# frontpanel-new.net
KiCad netlist of a schematic drawn in EAGLE
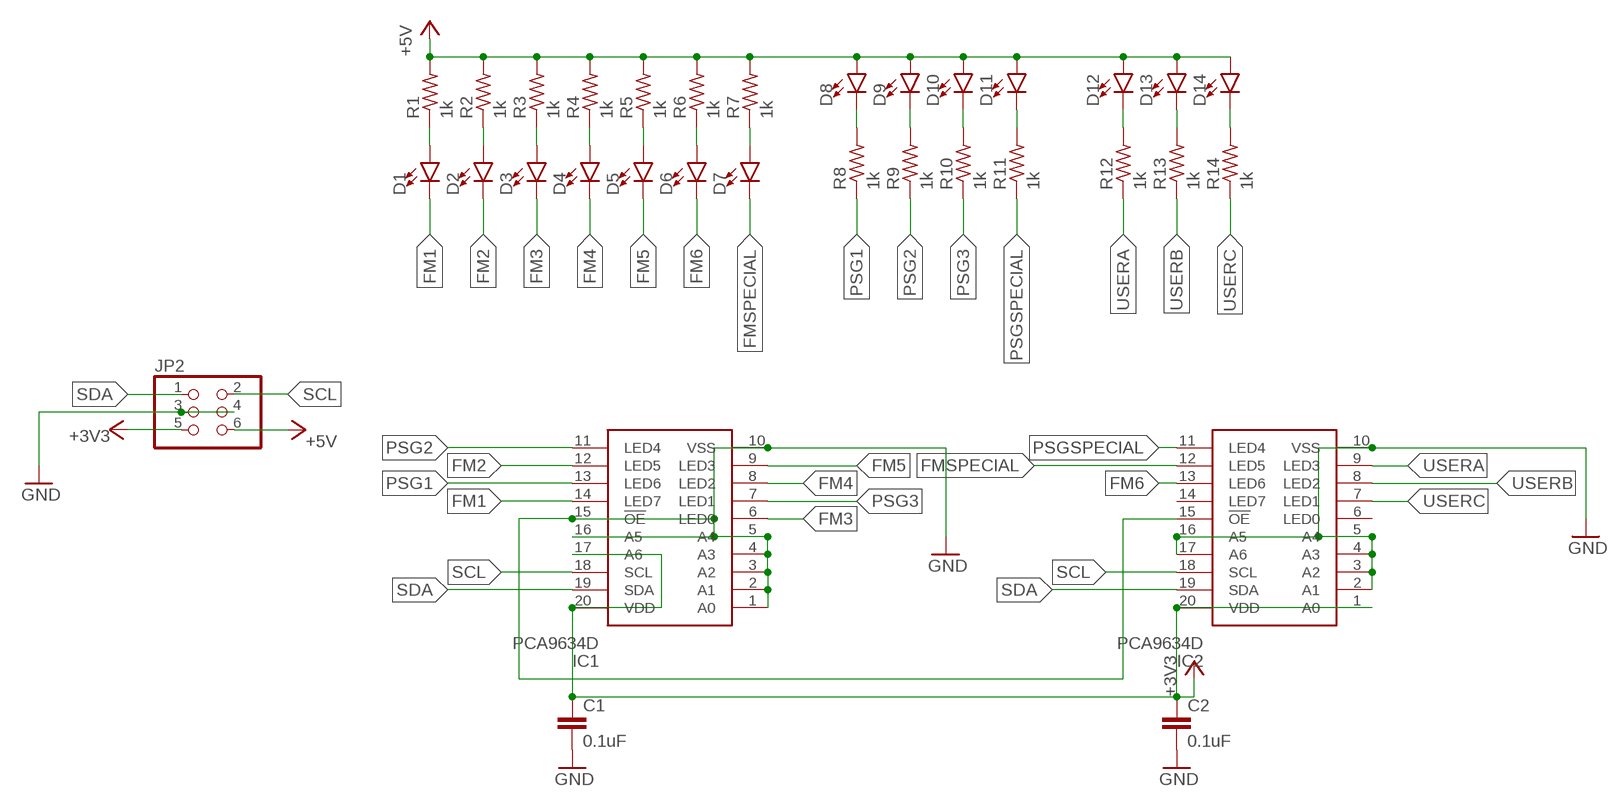
[diagram p0: schematic, sheet 1]

(export (version "E")
  (design (tool "Eeschema 10.0.6"))
  (components
    (comp (ref "C1")
      (value "0.1uF")
      (footprint "eagle-import:C0805")
      (libsource (lib "eagle-import") (part "C-EUC0805"))
    )
    (comp (ref "C2")
      (value "0.1uF")
      (footprint "eagle-import:C0805")
      (libsource (lib "eagle-import") (part "C-EUC0805"))
    )
    (comp (ref "D1")
      (value "AM2520")
      (footprint "eagle-import:AM2520HOLE")
      (libsource (lib "eagle-import") (part "AM2520"))
    )
    (comp (ref "D2")
      (value "AM2520")
      (footprint "eagle-import:AM2520HOLE")
      (libsource (lib "eagle-import") (part "AM2520"))
    )
    (comp (ref "D3")
      (value "AM2520")
      (footprint "eagle-import:AM2520HOLE")
      (libsource (lib "eagle-import") (part "AM2520"))
    )
    (comp (ref "D4")
      (value "AM2520")
      (footprint "eagle-import:AM2520HOLE")
      (libsource (lib "eagle-import") (part "AM2520"))
    )
    (comp (ref "D5")
      (value "AM2520")
      (footprint "eagle-import:AM2520HOLE")
      (libsource (lib "eagle-import") (part "AM2520"))
    )
    (comp (ref "D6")
      (value "AM2520")
      (footprint "eagle-import:AM2520HOLE")
      (libsource (lib "eagle-import") (part "AM2520"))
    )
    (comp (ref "D7")
      (value "AM2520")
      (footprint "eagle-import:AM2520HOLE")
      (libsource (lib "eagle-import") (part "AM2520"))
    )
    (comp (ref "D8")
      (value "AM2520")
      (footprint "eagle-import:AM2520HOLE")
      (libsource (lib "eagle-import") (part "AM2520"))
    )
    (comp (ref "D9")
      (value "AM2520")
      (footprint "eagle-import:AM2520HOLE")
      (libsource (lib "eagle-import") (part "AM2520"))
    )
    (comp (ref "D10")
      (value "AM2520")
      (footprint "eagle-import:AM2520HOLE")
      (libsource (lib "eagle-import") (part "AM2520"))
    )
    (comp (ref "D11")
      (value "AM2520")
      (footprint "eagle-import:AM2520HOLE")
      (libsource (lib "eagle-import") (part "AM2520"))
    )
    (comp (ref "D12")
      (value "AM2520")
      (footprint "eagle-import:AM2520HOLE")
      (libsource (lib "eagle-import") (part "AM2520"))
    )
    (comp (ref "D13")
      (value "AM2520")
      (footprint "eagle-import:AM2520HOLE")
      (libsource (lib "eagle-import") (part "AM2520"))
    )
    (comp (ref "D14")
      (value "AM2520")
      (footprint "eagle-import:AM2520HOLE")
      (libsource (lib "eagle-import") (part "AM2520"))
    )
    (comp (ref "IC1")
      (value "PCA9634D")
      (footprint "eagle-import:SOIC127P1032X265-20N")
      (libsource (lib "eagle-import") (part "PCA9634D"))
    )
    (comp (ref "IC2")
      (value "PCA9634D")
      (footprint "eagle-import:SOIC127P1032X265-20N")
      (libsource (lib "eagle-import") (part "PCA9634D"))
    )
    (comp (ref "JP2")
      (value "PINHD-2X3SMT")
      (footprint "eagle-import:2X03_SMT")
      (libsource (lib "eagle-import") (part "PINHD-2X3SMT"))
    )
    (comp (ref "R1")
      (value "1k")
      (footprint "eagle-import:R0805")
      (libsource (lib "eagle-import") (part "R-US_R0805"))
    )
    (comp (ref "R2")
      (value "1k")
      (footprint "eagle-import:R0805")
      (libsource (lib "eagle-import") (part "R-US_R0805"))
    )
    (comp (ref "R3")
      (value "1k")
      (footprint "eagle-import:R0805")
      (libsource (lib "eagle-import") (part "R-US_R0805"))
    )
    (comp (ref "R4")
      (value "1k")
      (footprint "eagle-import:R0805")
      (libsource (lib "eagle-import") (part "R-US_R0805"))
    )
    (comp (ref "R5")
      (value "1k")
      (footprint "eagle-import:R0805")
      (libsource (lib "eagle-import") (part "R-US_R0805"))
    )
    (comp (ref "R6")
      (value "1k")
      (footprint "eagle-import:R0805")
      (libsource (lib "eagle-import") (part "R-US_R0805"))
    )
    (comp (ref "R7")
      (value "1k")
      (footprint "eagle-import:R0805")
      (libsource (lib "eagle-import") (part "R-US_R0805"))
    )
    (comp (ref "R8")
      (value "1k")
      (footprint "eagle-import:R0805")
      (libsource (lib "eagle-import") (part "R-US_R0805"))
    )
    (comp (ref "R9")
      (value "1k")
      (footprint "eagle-import:R0805")
      (libsource (lib "eagle-import") (part "R-US_R0805"))
    )
    (comp (ref "R10")
      (value "1k")
      (footprint "eagle-import:R0805")
      (libsource (lib "eagle-import") (part "R-US_R0805"))
    )
    (comp (ref "R11")
      (value "1k")
      (footprint "eagle-import:R0805")
      (libsource (lib "eagle-import") (part "R-US_R0805"))
    )
    (comp (ref "R12")
      (value "1k")
      (footprint "eagle-import:R0805")
      (libsource (lib "eagle-import") (part "R-US_R0805"))
    )
    (comp (ref "R13")
      (value "1k")
      (footprint "eagle-import:R0805")
      (libsource (lib "eagle-import") (part "R-US_R0805"))
    )
    (comp (ref "R14")
      (value "1k")
      (footprint "eagle-import:R0805")
      (libsource (lib "eagle-import") (part "R-US_R0805"))
    )
  )
  (nets
    (net (code "1") (name "+3V3") (class "Default")
      (node (ref "C1") (pin "1") (pinfunction "1_1") (pintype "passive"))
      (node (ref "C2") (pin "1") (pinfunction "1_1") (pintype "passive"))
      (node (ref "IC1") (pin "17") (pinfunction "A6_17") (pintype "bidirectional"))
      (node (ref "IC1") (pin "20") (pinfunction "VDD_20") (pintype "power_in"))
      (node (ref "IC2") (pin "1") (pinfunction "A0_1") (pintype "bidirectional"))
      (node (ref "IC2") (pin "20") (pinfunction "VDD_20") (pintype "power_in"))
      (node (ref "JP2") (pin "5") (pinfunction "5_5") (pintype "passive"))
    )
    (net (code "2") (name "+5V") (class "Default")
      (node (ref "D10") (pin "A") (pinfunction "A_A") (pintype "passive"))
      (node (ref "D11") (pin "A") (pinfunction "A_A") (pintype "passive"))
      (node (ref "D12") (pin "A") (pinfunction "A_A") (pintype "passive"))
      (node (ref "D13") (pin "A") (pinfunction "A_A") (pintype "passive"))
      (node (ref "D14") (pin "A") (pinfunction "A_A") (pintype "passive"))
      (node (ref "D8") (pin "A") (pinfunction "A_A") (pintype "passive"))
      (node (ref "D9") (pin "A") (pinfunction "A_A") (pintype "passive"))
      (node (ref "JP2") (pin "6") (pinfunction "6_6") (pintype "passive"))
      (node (ref "R1") (pin "2") (pinfunction "2_2") (pintype "passive"))
      (node (ref "R2") (pin "2") (pinfunction "2_2") (pintype "passive"))
      (node (ref "R3") (pin "2") (pinfunction "2_2") (pintype "passive"))
      (node (ref "R4") (pin "2") (pinfunction "2_2") (pintype "passive"))
      (node (ref "R5") (pin "2") (pinfunction "2_2") (pintype "passive"))
      (node (ref "R6") (pin "2") (pinfunction "2_2") (pintype "passive"))
      (node (ref "R7") (pin "2") (pinfunction "2_2") (pintype "passive"))
    )
    (net (code "3") (name "FM1") (class "Default")
      (node (ref "D1") (pin "C") (pinfunction "C_C") (pintype "passive"))
      (node (ref "IC1") (pin "14") (pinfunction "LED7_14") (pintype "bidirectional"))
    )
    (net (code "4") (name "FM2") (class "Default")
      (node (ref "D2") (pin "C") (pinfunction "C_C") (pintype "passive"))
      (node (ref "IC1") (pin "12") (pinfunction "LED5_12") (pintype "bidirectional"))
    )
    (net (code "5") (name "FM3") (class "Default")
      (node (ref "D3") (pin "C") (pinfunction "C_C") (pintype "passive"))
      (node (ref "IC1") (pin "6") (pinfunction "LED0_6") (pintype "bidirectional"))
    )
    (net (code "6") (name "FM4") (class "Default")
      (node (ref "D4") (pin "C") (pinfunction "C_C") (pintype "passive"))
      (node (ref "IC1") (pin "8") (pinfunction "LED2_8") (pintype "bidirectional"))
    )
    (net (code "7") (name "FM5") (class "Default")
      (node (ref "D5") (pin "C") (pinfunction "C_C") (pintype "passive"))
      (node (ref "IC1") (pin "9") (pinfunction "LED3_9") (pintype "bidirectional"))
    )
    (net (code "8") (name "FM6") (class "Default")
      (node (ref "D6") (pin "C") (pinfunction "C_C") (pintype "passive"))
      (node (ref "IC2") (pin "13") (pinfunction "LED6_13") (pintype "bidirectional"))
    )
    (net (code "9") (name "FMSPECIAL") (class "Default")
      (node (ref "D7") (pin "C") (pinfunction "C_C") (pintype "passive"))
      (node (ref "IC2") (pin "12") (pinfunction "LED5_12") (pintype "bidirectional"))
    )
    (net (code "10") (name "GND") (class "Default")
      (node (ref "C1") (pin "2") (pinfunction "2_2") (pintype "passive"))
      (node (ref "C2") (pin "2") (pinfunction "2_2") (pintype "passive"))
      (node (ref "IC1") (pin "1") (pinfunction "A0_1") (pintype "bidirectional"))
      (node (ref "IC1") (pin "10") (pinfunction "VSS_10") (pintype "power_in"))
      (node (ref "IC1") (pin "15") (pinfunction "~{OE}_15") (pintype "bidirectional"))
      (node (ref "IC1") (pin "16") (pinfunction "A5_16") (pintype "bidirectional"))
      (node (ref "IC1") (pin "2") (pinfunction "A1_2") (pintype "bidirectional"))
      (node (ref "IC1") (pin "3") (pinfunction "A2_3") (pintype "bidirectional"))
      (node (ref "IC1") (pin "4") (pinfunction "A3_4") (pintype "bidirectional"))
      (node (ref "IC1") (pin "5") (pinfunction "A4_5") (pintype "bidirectional"))
      (node (ref "IC2") (pin "10") (pinfunction "VSS_10") (pintype "power_in"))
      (node (ref "IC2") (pin "15") (pinfunction "~{OE}_15") (pintype "bidirectional"))
      (node (ref "IC2") (pin "16") (pinfunction "A5_16") (pintype "bidirectional"))
      (node (ref "IC2") (pin "17") (pinfunction "A6_17") (pintype "bidirectional"))
      (node (ref "IC2") (pin "2") (pinfunction "A1_2") (pintype "bidirectional"))
      (node (ref "IC2") (pin "3") (pinfunction "A2_3") (pintype "bidirectional"))
      (node (ref "IC2") (pin "4") (pinfunction "A3_4") (pintype "bidirectional"))
      (node (ref "IC2") (pin "5") (pinfunction "A4_5") (pintype "bidirectional"))
      (node (ref "JP2") (pin "3") (pinfunction "3_3") (pintype "passive"))
      (node (ref "JP2") (pin "4") (pinfunction "4_4") (pintype "passive"))
    )
    (net (code "11") (name "Net-(D1-PadA)") (class "Default")
      (node (ref "D1") (pin "A") (pinfunction "A_A") (pintype "passive"))
      (node (ref "R1") (pin "1") (pinfunction "1_1") (pintype "passive"))
    )
    (net (code "12") (name "Net-(D2-PadA)") (class "Default")
      (node (ref "D2") (pin "A") (pinfunction "A_A") (pintype "passive"))
      (node (ref "R2") (pin "1") (pinfunction "1_1") (pintype "passive"))
    )
    (net (code "13") (name "Net-(D3-PadA)") (class "Default")
      (node (ref "D3") (pin "A") (pinfunction "A_A") (pintype "passive"))
      (node (ref "R3") (pin "1") (pinfunction "1_1") (pintype "passive"))
    )
    (net (code "14") (name "Net-(D4-PadA)") (class "Default")
      (node (ref "D4") (pin "A") (pinfunction "A_A") (pintype "passive"))
      (node (ref "R4") (pin "1") (pinfunction "1_1") (pintype "passive"))
    )
    (net (code "15") (name "Net-(D5-PadA)") (class "Default")
      (node (ref "D5") (pin "A") (pinfunction "A_A") (pintype "passive"))
      (node (ref "R5") (pin "1") (pinfunction "1_1") (pintype "passive"))
    )
    (net (code "16") (name "Net-(D6-PadA)") (class "Default")
      (node (ref "D6") (pin "A") (pinfunction "A_A") (pintype "passive"))
      (node (ref "R6") (pin "1") (pinfunction "1_1") (pintype "passive"))
    )
    (net (code "17") (name "Net-(D7-PadA)") (class "Default")
      (node (ref "D7") (pin "A") (pinfunction "A_A") (pintype "passive"))
      (node (ref "R7") (pin "1") (pinfunction "1_1") (pintype "passive"))
    )
    (net (code "18") (name "Net-(D8-PadC)") (class "Default")
      (node (ref "D8") (pin "C") (pinfunction "C_C") (pintype "passive"))
      (node (ref "R8") (pin "2") (pinfunction "2_2") (pintype "passive"))
    )
    (net (code "19") (name "Net-(D9-PadC)") (class "Default")
      (node (ref "D9") (pin "C") (pinfunction "C_C") (pintype "passive"))
      (node (ref "R9") (pin "2") (pinfunction "2_2") (pintype "passive"))
    )
    (net (code "20") (name "Net-(D10-PadC)") (class "Default")
      (node (ref "D10") (pin "C") (pinfunction "C_C") (pintype "passive"))
      (node (ref "R10") (pin "2") (pinfunction "2_2") (pintype "passive"))
    )
    (net (code "21") (name "Net-(D11-PadC)") (class "Default")
      (node (ref "D11") (pin "C") (pinfunction "C_C") (pintype "passive"))
      (node (ref "R11") (pin "2") (pinfunction "2_2") (pintype "passive"))
    )
    (net (code "22") (name "Net-(D12-PadC)") (class "Default")
      (node (ref "D12") (pin "C") (pinfunction "C_C") (pintype "passive"))
      (node (ref "R12") (pin "2") (pinfunction "2_2") (pintype "passive"))
    )
    (net (code "23") (name "Net-(D13-PadC)") (class "Default")
      (node (ref "D13") (pin "C") (pinfunction "C_C") (pintype "passive"))
      (node (ref "R13") (pin "2") (pinfunction "2_2") (pintype "passive"))
    )
    (net (code "24") (name "Net-(D14-PadC)") (class "Default")
      (node (ref "D14") (pin "C") (pinfunction "C_C") (pintype "passive"))
      (node (ref "R14") (pin "2") (pinfunction "2_2") (pintype "passive"))
    )
    (net (code "25") (name "PSG1") (class "Default")
      (node (ref "IC1") (pin "13") (pinfunction "LED6_13") (pintype "bidirectional"))
      (node (ref "R8") (pin "1") (pinfunction "1_1") (pintype "passive"))
    )
    (net (code "26") (name "PSG2") (class "Default")
      (node (ref "IC1") (pin "11") (pinfunction "LED4_11") (pintype "bidirectional"))
      (node (ref "R9") (pin "1") (pinfunction "1_1") (pintype "passive"))
    )
    (net (code "27") (name "PSG3") (class "Default")
      (node (ref "IC1") (pin "7") (pinfunction "LED1_7") (pintype "bidirectional"))
      (node (ref "R10") (pin "1") (pinfunction "1_1") (pintype "passive"))
    )
    (net (code "28") (name "PSGSPECIAL") (class "Default")
      (node (ref "IC2") (pin "11") (pinfunction "LED4_11") (pintype "bidirectional"))
      (node (ref "R11") (pin "1") (pinfunction "1_1") (pintype "passive"))
    )
    (net (code "29") (name "SCL") (class "Default")
      (node (ref "IC1") (pin "18") (pinfunction "SCL_18") (pintype "bidirectional"))
      (node (ref "IC2") (pin "18") (pinfunction "SCL_18") (pintype "bidirectional"))
      (node (ref "JP2") (pin "2") (pinfunction "2_2") (pintype "passive"))
    )
    (net (code "30") (name "SDA") (class "Default")
      (node (ref "IC1") (pin "19") (pinfunction "SDA_19") (pintype "bidirectional"))
      (node (ref "IC2") (pin "19") (pinfunction "SDA_19") (pintype "bidirectional"))
      (node (ref "JP2") (pin "1") (pinfunction "1_1") (pintype "passive"))
    )
    (net (code "31") (name "USERA") (class "Default")
      (node (ref "IC2") (pin "9") (pinfunction "LED3_9") (pintype "bidirectional"))
      (node (ref "R12") (pin "1") (pinfunction "1_1") (pintype "passive"))
    )
    (net (code "32") (name "USERB") (class "Default")
      (node (ref "IC2") (pin "8") (pinfunction "LED2_8") (pintype "bidirectional"))
      (node (ref "R13") (pin "1") (pinfunction "1_1") (pintype "passive"))
    )
    (net (code "33") (name "USERC") (class "Default")
      (node (ref "IC2") (pin "7") (pinfunction "LED1_7") (pintype "bidirectional"))
      (node (ref "R14") (pin "1") (pinfunction "1_1") (pintype "passive"))
    )
    (net (code "34") (name "unconnected-(IC2-LED0-Pad6)") (class "Default")
      (node (ref "IC2") (pin "6") (pinfunction "LED0_6") (pintype "bidirectional"))
    )
    (net (code "35") (name "unconnected-(IC2-LED7-Pad14)") (class "Default")
      (node (ref "IC2") (pin "14") (pinfunction "LED7_14") (pintype "bidirectional"))
    )
  )
)
